# Pack_monitoring.net
KiCad netlist of a schematic drawn in Altium Designer
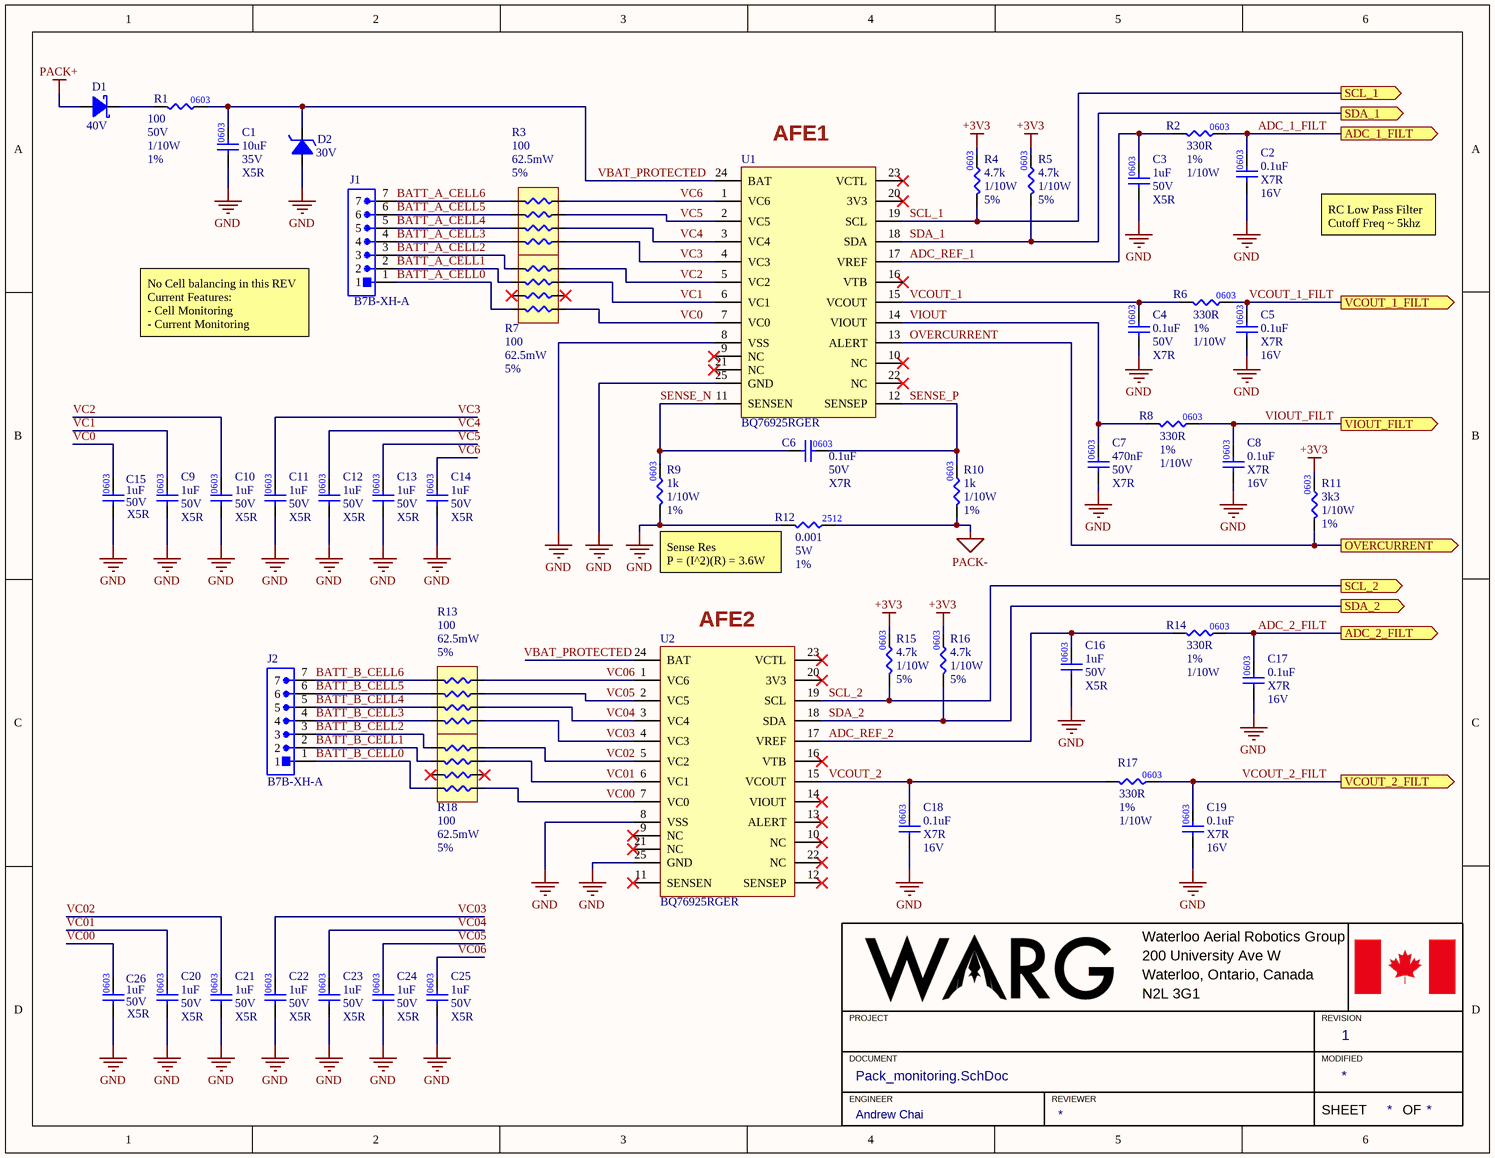
[diagram p0: Pack_monitoring.SchDoc]

(export (version "E")
  (design (tool "Eeschema 10.0.6"))
  (components
    (comp (ref "C1")
      (value "10uF")
      (footprint ".CAP_0603-Footprint-1")
      (fields
        (field (name "RATED DC VOLTAGE (URDC)") "35V")
        (field (name "TEMPERATURE CHARACTERISTICS CODE") "X5R")
        (field (name "Comment") "GRM188R6YA106MA73J")
      )
      (libsource (lib "WARG") (part ".CAP_0603-Symbol-1"))
    )
    (comp (ref "C2")
      (value "0.1uF")
      (footprint ".CAP_0603-Footprint-1")
      (description "CAP CER 0.1uF 16V X7R 0603")
      (fields
        (field (name "TEMPERATURE COEFFICIENT") "X7R")
        (field (name "VOLTAGE") "16V")
        (field (name "Comment") "GCM188R71C104KA37D")
      )
      (libsource (lib "WARG") (part ".CAP_0603-Symbol-1"))
    )
    (comp (ref "C3")
      (value "1uF")
      (footprint ".CAP_0603-Footprint-1")
      (description "CAP CER 1UF 50V X5R 0603")
      (fields
        (field (name "VOLTAGE RATING") "50V")
        (field (name "TEMPERATURE CHARACTERISTICS CODE") "X5R")
        (field (name "TOLERANCE") "10%")
        (field (name "Comment") "GRT188R61H105KE13D")
      )
      (libsource (lib "WARG") (part "CAP"))
    )
    (comp (ref "C4")
      (value "GCM188R71H104KA57D")
      (footprint "CAP0603")
      (description "CAP CER 0.1uF 50V X7R 0603")
      (fields
        (field (name "VOLTAGE") "50V")
        (field (name "DIELECTRIC") "X7R")
        (field (name "CAPACITANCE") "0.1uF")
        (field (name "TOLERANCE") "10%")
      )
      (libsource (lib "WARG") (part "CAP-NP-2"))
    )
    (comp (ref "C5")
      (value "0.1uF")
      (footprint ".CAP_0603-Footprint-1")
      (description "CAP CER 0.1uF 16V X7R 0603")
      (fields
        (field (name "TEMPERATURE COEFFICIENT") "X7R")
        (field (name "VOLTAGE") "16V")
        (field (name "Comment") "GCM188R71C104KA37D")
      )
      (libsource (lib "WARG") (part ".CAP_0603-Symbol-1"))
    )
    (comp (ref "C6")
      (value "GCM188R71H104KA57D")
      (footprint "CAP0603")
      (description "CAP CER 0.1uF 50V X7R 0603")
      (fields
        (field (name "VOLTAGE") "50V")
        (field (name "DIELECTRIC") "X7R")
        (field (name "CAPACITANCE") "0.1uF")
        (field (name "TOLERANCE") "10%")
      )
      (libsource (lib "WARG") (part "CAP-NP-2"))
    )
    (comp (ref "C7")
      (value "UMK107B7474KA-TR")
      (footprint "FP-0603-L_1_6_0_1-W_0_8_0-IPC_A")
      (description "0603 0.47 uF 50 V ±10% Tolerance X7R Multilayer Ceramic Capacitor")
      (fields
        (field (name "TOLERANCE") "10%")
        (field (name "DIELECTRIC") "X7R")
        (field (name "VOLTAGE") "50V")
        (field (name "CAPACITANCE") "470nF")
        (field (name "VOLTAGE RATING") "50V")
      )
      (libsource (lib "WARG") (part "02cd4be3c70576c341d710602a673aa"))
    )
    (comp (ref "C8")
      (value "0.1uF")
      (footprint ".CAP_0603-Footprint-1")
      (description "CAP CER 0.1uF 16V X7R 0603")
      (fields
        (field (name "TEMPERATURE COEFFICIENT") "X7R")
        (field (name "VOLTAGE") "16V")
        (field (name "Comment") "GCM188R71C104KA37D")
      )
      (libsource (lib "WARG") (part ".CAP_0603-Symbol-1"))
    )
    (comp (ref "C9")
      (value "1uF")
      (footprint ".CAP_0603-Footprint-1")
      (description "CAP CER 1UF 50V X5R 0603")
      (fields
        (field (name "VOLTAGE RATING") "50V")
        (field (name "TEMPERATURE CHARACTERISTICS CODE") "X5R")
        (field (name "TOLERANCE") "10%")
        (field (name "Comment") "GRT188R61H105KE13D")
      )
      (libsource (lib "WARG") (part "CAP"))
    )
    (comp (ref "C10")
      (value "1uF")
      (footprint ".CAP_0603-Footprint-1")
      (description "CAP CER 1UF 50V X5R 0603")
      (fields
        (field (name "VOLTAGE RATING") "50V")
        (field (name "TEMPERATURE CHARACTERISTICS CODE") "X5R")
        (field (name "TOLERANCE") "10%")
        (field (name "Comment") "GRT188R61H105KE13D")
      )
      (libsource (lib "WARG") (part "CAP"))
    )
    (comp (ref "C11")
      (value "1uF")
      (footprint ".CAP_0603-Footprint-1")
      (description "CAP CER 1UF 50V X5R 0603")
      (fields
        (field (name "VOLTAGE RATING") "50V")
        (field (name "TEMPERATURE CHARACTERISTICS CODE") "X5R")
        (field (name "TOLERANCE") "10%")
        (field (name "Comment") "GRT188R61H105KE13D")
      )
      (libsource (lib "WARG") (part "CAP"))
    )
    (comp (ref "C12")
      (value "1uF")
      (footprint ".CAP_0603-Footprint-1")
      (description "CAP CER 1UF 50V X5R 0603")
      (fields
        (field (name "VOLTAGE RATING") "50V")
        (field (name "TEMPERATURE CHARACTERISTICS CODE") "X5R")
        (field (name "TOLERANCE") "10%")
        (field (name "Comment") "GRT188R61H105KE13D")
      )
      (libsource (lib "WARG") (part "CAP"))
    )
    (comp (ref "C13")
      (value "1uF")
      (footprint ".CAP_0603-Footprint-1")
      (description "CAP CER 1UF 50V X5R 0603")
      (fields
        (field (name "VOLTAGE RATING") "50V")
        (field (name "TEMPERATURE CHARACTERISTICS CODE") "X5R")
        (field (name "TOLERANCE") "10%")
        (field (name "Comment") "GRT188R61H105KE13D")
      )
      (libsource (lib "WARG") (part "CAP"))
    )
    (comp (ref "C14")
      (value "1uF")
      (footprint ".CAP_0603-Footprint-1")
      (description "CAP CER 1UF 50V X5R 0603")
      (fields
        (field (name "VOLTAGE RATING") "50V")
        (field (name "TEMPERATURE CHARACTERISTICS CODE") "X5R")
        (field (name "TOLERANCE") "10%")
        (field (name "Comment") "GRT188R61H105KE13D")
      )
      (libsource (lib "WARG") (part "CAP"))
    )
    (comp (ref "C15")
      (value "1uF")
      (footprint ".CAP_0603-Footprint-1")
      (description "CAP CER 1UF 50V X5R 0603")
      (fields
        (field (name "VOLTAGE RATING") "50V")
        (field (name "TEMPERATURE CHARACTERISTICS CODE") "X5R")
        (field (name "TOLERANCE") "10%")
        (field (name "Comment") "GRT188R61H105KE13D")
      )
      (libsource (lib "WARG") (part "CAP"))
    )
    (comp (ref "C16")
      (value "1uF")
      (footprint ".CAP_0603-Footprint-1")
      (description "CAP CER 1UF 50V X5R 0603")
      (fields
        (field (name "VOLTAGE RATING") "50V")
        (field (name "TEMPERATURE CHARACTERISTICS CODE") "X5R")
        (field (name "TOLERANCE") "10%")
        (field (name "Comment") "GRT188R61H105KE13D")
      )
      (libsource (lib "WARG") (part "CAP"))
    )
    (comp (ref "C17")
      (value "0.1uF")
      (footprint ".CAP_0603-Footprint-1")
      (description "CAP CER 0.1uF 16V X7R 0603")
      (fields
        (field (name "TEMPERATURE COEFFICIENT") "X7R")
        (field (name "VOLTAGE") "16V")
        (field (name "Comment") "GCM188R71C104KA37D")
      )
      (libsource (lib "WARG") (part ".CAP_0603-Symbol-1"))
    )
    (comp (ref "C18")
      (value "0.1uF")
      (footprint ".CAP_0603-Footprint-1")
      (description "CAP CER 0.1uF 16V X7R 0603")
      (fields
        (field (name "TEMPERATURE COEFFICIENT") "X7R")
        (field (name "VOLTAGE") "16V")
        (field (name "Comment") "GCM188R71C104KA37D")
      )
      (libsource (lib "WARG") (part ".CAP_0603-Symbol-1"))
    )
    (comp (ref "C19")
      (value "0.1uF")
      (footprint ".CAP_0603-Footprint-1")
      (description "CAP CER 0.1uF 16V X7R 0603")
      (fields
        (field (name "TEMPERATURE COEFFICIENT") "X7R")
        (field (name "VOLTAGE") "16V")
        (field (name "Comment") "GCM188R71C104KA37D")
      )
      (libsource (lib "WARG") (part ".CAP_0603-Symbol-1"))
    )
    (comp (ref "C20")
      (value "1uF")
      (footprint ".CAP_0603-Footprint-1")
      (description "CAP CER 1UF 50V X5R 0603")
      (fields
        (field (name "VOLTAGE RATING") "50V")
        (field (name "TEMPERATURE CHARACTERISTICS CODE") "X5R")
        (field (name "TOLERANCE") "10%")
        (field (name "Comment") "GRT188R61H105KE13D")
      )
      (libsource (lib "WARG") (part "CAP"))
    )
    (comp (ref "C21")
      (value "1uF")
      (footprint ".CAP_0603-Footprint-1")
      (description "CAP CER 1UF 50V X5R 0603")
      (fields
        (field (name "VOLTAGE RATING") "50V")
        (field (name "TEMPERATURE CHARACTERISTICS CODE") "X5R")
        (field (name "TOLERANCE") "10%")
        (field (name "Comment") "GRT188R61H105KE13D")
      )
      (libsource (lib "WARG") (part "CAP"))
    )
    (comp (ref "C22")
      (value "1uF")
      (footprint ".CAP_0603-Footprint-1")
      (description "CAP CER 1UF 50V X5R 0603")
      (fields
        (field (name "VOLTAGE RATING") "50V")
        (field (name "TEMPERATURE CHARACTERISTICS CODE") "X5R")
        (field (name "TOLERANCE") "10%")
        (field (name "Comment") "GRT188R61H105KE13D")
      )
      (libsource (lib "WARG") (part "CAP"))
    )
    (comp (ref "C23")
      (value "1uF")
      (footprint ".CAP_0603-Footprint-1")
      (description "CAP CER 1UF 50V X5R 0603")
      (fields
        (field (name "VOLTAGE RATING") "50V")
        (field (name "TEMPERATURE CHARACTERISTICS CODE") "X5R")
        (field (name "TOLERANCE") "10%")
        (field (name "Comment") "GRT188R61H105KE13D")
      )
      (libsource (lib "WARG") (part "CAP"))
    )
    (comp (ref "C24")
      (value "1uF")
      (footprint ".CAP_0603-Footprint-1")
      (description "CAP CER 1UF 50V X5R 0603")
      (fields
        (field (name "VOLTAGE RATING") "50V")
        (field (name "TEMPERATURE CHARACTERISTICS CODE") "X5R")
        (field (name "TOLERANCE") "10%")
        (field (name "Comment") "GRT188R61H105KE13D")
      )
      (libsource (lib "WARG") (part "CAP"))
    )
    (comp (ref "C25")
      (value "1uF")
      (footprint ".CAP_0603-Footprint-1")
      (description "CAP CER 1UF 50V X5R 0603")
      (fields
        (field (name "VOLTAGE RATING") "50V")
        (field (name "TEMPERATURE CHARACTERISTICS CODE") "X5R")
        (field (name "TOLERANCE") "10%")
        (field (name "Comment") "GRT188R61H105KE13D")
      )
      (libsource (lib "WARG") (part "CAP"))
    )
    (comp (ref "C26")
      (value "1uF")
      (footprint ".CAP_0603-Footprint-1")
      (description "CAP CER 1UF 50V X5R 0603")
      (fields
        (field (name "VOLTAGE RATING") "50V")
        (field (name "TEMPERATURE CHARACTERISTICS CODE") "X5R")
        (field (name "TOLERANCE") "10%")
        (field (name "Comment") "GRT188R61H105KE13D")
      )
      (libsource (lib "WARG") (part "CAP"))
    )
    (comp (ref "D1")
      (value "MBR0540T1G")
      (footprint "Copy of .SCHOTTKY-Footprint-1")
      (description "DIODE SCHOTTKY 40V 500MA SOD123")
      (fields (field (name "REP PK REVERSE VOLTAGE-MAX") "40V"))
      (libsource (lib "WARG") (part ".SCHOTTKY-Symbol-1"))
    )
    (comp (ref "D2")
      (value "BZT52C30-13")
      (footprint "BZT52C30-13-Footprint-1")
      (description "Zener Diode, 30V V(Z), 6.67%, 0.5W, Silicon, Unidirectional")
      (fields (field (name "REFERENCE VOLTAGE-NOM") "30V"))
      (libsource (lib "WARG") (part ".ZENER-Symbol-1"))
    )
    (comp (ref "J1")
      (value "B7B-XH-A")
      (footprint "B7B-XH-A")
      (description "Header B7B-XH-A, 2.50mm, 7-contacts, top entry, THT /500/box")
      (fields (field (name "MF") "JST Sales"))
      (libsource (lib "WARG") (part "B7B-XH-A"))
    )
    (comp (ref "J2")
      (value "B7B-XH-A")
      (footprint "B7B-XH-A")
      (description "Header B7B-XH-A, 2.50mm, 7-contacts, top entry, THT /500/box")
      (fields (field (name "MF") "JST Sales"))
      (libsource (lib "WARG") (part "B7B-XH-A"))
    )
    (comp (ref "R1")
      (value "RC0603FR-07100RL")
      (footprint ".RES_0603-Footprint-1")
      (description "RES 100 OHM 1% 1/10W 0603")
      (fields
        (field (name "RESISTANCE") "100")
        (field (name "VOLTAGE RATING (DC)") "50V")
        (field (name "POWER RATING") "1/10W")
        (field (name "TOLERANCE") "1%")
      )
      (libsource (lib "") (part ".RES_0603-Symbol-1_1"))
    )
    (comp (ref "R2")
      (value "330R")
      (footprint ".RES_0603-Footprint-1")
      (fields
        (field (name "POWER") "1/10W")
        (field (name "TOLERANCE") "1%")
        (field (name "Comment") "AF0603FR-07330RL")
      )
      (libsource (lib "") (part ".RES_0603-Symbol-1_1"))
    )
    (comp (ref "R3")
      (value "100")
      (footprint ".RES_0603-Footprint-1")
      (description "YC124 Series 4 Elements 100 Ohms 5 % Case 4 x 0402 SMD Chip Resistor Network")
      (fields
        (field (name "POWER") "62.5mW")
        (field (name "TOLERANCE") "5%")
        (field (name "Comment") "YC124JR-07100RL")
      )
      (libsource (lib "WARG") (part "YC124-JR-07100RL"))
    )
    (comp (ref "R4")
      (value "4.7k")
      (footprint ".RES_0603-Footprint-1")
      (description "RES 4.7K OHM 5% 1/10W 0603")
      (fields
        (field (name "RESISTANCE TOLERANCE") "5%")
        (field (name "POWER RATING") "1/10W")
        (field (name "Comment") "RC0603JR-074K7L")
      )
      (libsource (lib "") (part ".RES_0603-Symbol-1_1"))
    )
    (comp (ref "R5")
      (value "4.7k")
      (footprint ".RES_0603-Footprint-1")
      (description "RES 4.7K OHM 5% 1/10W 0603")
      (fields
        (field (name "RESISTANCE TOLERANCE") "5%")
        (field (name "POWER RATING") "1/10W")
        (field (name "Comment") "RC0603JR-074K7L")
      )
      (libsource (lib "") (part ".RES_0603-Symbol-1_1"))
    )
    (comp (ref "R6")
      (value "330R")
      (footprint ".RES_0603-Footprint-1")
      (fields
        (field (name "POWER") "1/10W")
        (field (name "TOLERANCE") "1%")
        (field (name "Comment") "AF0603FR-07330RL")
      )
      (libsource (lib "") (part ".RES_0603-Symbol-1_1"))
    )
    (comp (ref "R7")
      (value "100")
      (footprint ".RES_0603-Footprint-1")
      (description "YC124 Series 4 Elements 100 Ohms 5 % Case 4 x 0402 SMD Chip Resistor Network")
      (fields
        (field (name "POWER") "62.5mW")
        (field (name "TOLERANCE") "5%")
        (field (name "Comment") "YC124JR-07100RL")
      )
      (libsource (lib "WARG") (part "YC124-JR-07100RL"))
    )
    (comp (ref "R8")
      (value "330R")
      (footprint ".RES_0603-Footprint-1")
      (fields
        (field (name "POWER") "1/10W")
        (field (name "TOLERANCE") "1%")
        (field (name "Comment") "AF0603FR-07330RL")
      )
      (libsource (lib "") (part ".RES_0603-Symbol-1_1"))
    )
    (comp (ref "R9")
      (value "1k")
      (footprint ".RES_0603-Footprint-1")
      (description "RES 1k OHM 1% 1/10W 0603")
      (fields
        (field (name "POWER") "1/10W")
        (field (name "TOLERANCE") "1%")
        (field (name "Comment") "RC0603FR-071KL")
      )
      (libsource (lib "") (part ".RES_0603-Symbol-1_1"))
    )
    (comp (ref "R10")
      (value "1k")
      (footprint ".RES_0603-Footprint-1")
      (description "RES 1k OHM 1% 1/10W 0603")
      (fields
        (field (name "POWER") "1/10W")
        (field (name "TOLERANCE") "1%")
        (field (name "Comment") "RC0603FR-071KL")
      )
      (libsource (lib "") (part ".RES_0603-Symbol-1_1"))
    )
    (comp (ref "R11")
      (value "3k3")
      (footprint ".RES_0603-Footprint-1")
      (description "RES 3.3K OHM 1% 1/10W 0603")
      (fields
        (field (name "POWER") "1/10W")
        (field (name "TOLERANCE") "1%")
        (field (name "Comment") "RC0603FR-103K3L")
      )
      (libsource (lib "") (part ".RES_0603-Symbol-1_1"))
    )
    (comp (ref "R12")
      (value "0.001")
      (footprint ".RES_0603-Footprint-1")
      (description "Fixed Resistor, Metal Strip, 5W, 0.001ohm, 1% +/-Tol, 50ppm/Cel, Surface Mount, 2512")
      (fields
        (field (name "TOLERANCE") "1%")
        (field (name "POWER") "5W")
        (field (name "Comment") "CSS2H-2512R-1L00F")
      )
      (libsource (lib "WARG") (part ".RES_0603-Symbol-1"))
    )
    (comp (ref "R13")
      (value "100")
      (footprint ".RES_0603-Footprint-1")
      (description "YC124 Series 4 Elements 100 Ohms 5 % Case 4 x 0402 SMD Chip Resistor Network")
      (fields
        (field (name "POWER") "62.5mW")
        (field (name "TOLERANCE") "5%")
        (field (name "Comment") "YC124JR-07100RL")
      )
      (libsource (lib "WARG") (part "YC124-JR-07100RL"))
    )
    (comp (ref "R14")
      (value "330R")
      (footprint ".RES_0603-Footprint-1")
      (fields
        (field (name "POWER") "1/10W")
        (field (name "TOLERANCE") "1%")
        (field (name "Comment") "AF0603FR-07330RL")
      )
      (libsource (lib "") (part ".RES_0603-Symbol-1_1"))
    )
    (comp (ref "R15")
      (value "4.7k")
      (footprint ".RES_0603-Footprint-1")
      (description "RES 4.7K OHM 5% 1/10W 0603")
      (fields
        (field (name "RESISTANCE TOLERANCE") "5%")
        (field (name "POWER RATING") "1/10W")
        (field (name "Comment") "RC0603JR-074K7L")
      )
      (libsource (lib "") (part ".RES_0603-Symbol-1_1"))
    )
    (comp (ref "R16")
      (value "4.7k")
      (footprint ".RES_0603-Footprint-1")
      (description "RES 4.7K OHM 5% 1/10W 0603")
      (fields
        (field (name "RESISTANCE TOLERANCE") "5%")
        (field (name "POWER RATING") "1/10W")
        (field (name "Comment") "RC0603JR-074K7L")
      )
      (libsource (lib "") (part ".RES_0603-Symbol-1_1"))
    )
    (comp (ref "R17")
      (value "330R")
      (footprint ".RES_0603-Footprint-1")
      (fields
        (field (name "POWER") "1/10W")
        (field (name "TOLERANCE") "1%")
        (field (name "Comment") "AF0603FR-07330RL")
      )
      (libsource (lib "") (part ".RES_0603-Symbol-1_1"))
    )
    (comp (ref "R18")
      (value "100")
      (footprint ".RES_0603-Footprint-1")
      (description "YC124 Series 4 Elements 100 Ohms 5 % Case 4 x 0402 SMD Chip Resistor Network")
      (fields
        (field (name "POWER") "62.5mW")
        (field (name "TOLERANCE") "5%")
        (field (name "Comment") "YC124JR-07100RL")
      )
      (libsource (lib "WARG") (part "YC124-JR-07100RL"))
    )
    (comp (ref "U1")
      (value "BQ76925RGER")
      (footprint "QFN50P400X400X100_HS-25N")
      (description "Power Supply Support Circuit, Adjustable, 1 Channel, PQCC24")
      (libsource (lib "WARG") (part "BQ76925PWR"))
    )
    (comp (ref "U2")
      (value "BQ76925RGER")
      (footprint "QFN50P400X400X100_HS-25N")
      (description "Power Supply Support Circuit, Adjustable, 1 Channel, PQCC24")
      (libsource (lib "WARG") (part "BQ76925PWR"))
    )
  )
  (nets
    (net (code "1") (name "+3V3") (class "Default")
      (node (ref "R11") (pin "2") (pinfunction "2_2") (pintype "passive"))
      (node (ref "R15") (pin "2") (pinfunction "2_2") (pintype "passive"))
      (node (ref "R16") (pin "2") (pinfunction "2_2") (pintype "passive"))
      (node (ref "R4") (pin "2") (pinfunction "2_2") (pintype "passive"))
      (node (ref "R5") (pin "2") (pinfunction "2_2") (pintype "passive"))
    )
    (net (code "2") (name "/ADC_1_FILT") (class "Default")
      (node (ref "C2") (pin "2") (pinfunction "2_2") (pintype "passive"))
      (node (ref "R2") (pin "2") (pinfunction "2_2") (pintype "passive"))
    )
    (net (code "3") (name "/ADC_2_FILT") (class "Default")
      (node (ref "C17") (pin "2") (pinfunction "2_2") (pintype "passive"))
      (node (ref "R14") (pin "2") (pinfunction "2_2") (pintype "passive"))
    )
    (net (code "4") (name "/ADC_REF_1") (class "Default")
      (node (ref "C3") (pin "2") (pinfunction "2_2") (pintype "passive"))
      (node (ref "R2") (pin "1") (pinfunction "1_1") (pintype "passive"))
      (node (ref "U1") (pin "17") (pinfunction "VREF_17") (pintype "passive"))
    )
    (net (code "5") (name "/ADC_REF_2") (class "Default")
      (node (ref "C16") (pin "2") (pinfunction "2_2") (pintype "passive"))
      (node (ref "R14") (pin "1") (pinfunction "1_1") (pintype "passive"))
      (node (ref "U2") (pin "17") (pinfunction "VREF_17") (pintype "passive"))
    )
    (net (code "6") (name "/BATT_A_CELL0") (class "Default")
      (node (ref "J1") (pin "1") (pinfunction "1_1") (pintype "passive"))
      (node (ref "R7") (pin "7") (pinfunction "7_7") (pintype "passive"))
    )
    (net (code "7") (name "/BATT_A_CELL1") (class "Default")
      (node (ref "J1") (pin "2") (pinfunction "2_2") (pintype "passive"))
      (node (ref "R7") (pin "3") (pinfunction "3_3") (pintype "passive"))
    )
    (net (code "8") (name "/BATT_A_CELL2") (class "Default")
      (node (ref "J1") (pin "3") (pinfunction "3_3") (pintype "passive"))
      (node (ref "R7") (pin "1") (pinfunction "1_1") (pintype "passive"))
    )
    (net (code "9") (name "/BATT_A_CELL3") (class "Default")
      (node (ref "J1") (pin "4") (pinfunction "4_4") (pintype "passive"))
      (node (ref "R3") (pin "7") (pinfunction "7_7") (pintype "passive"))
    )
    (net (code "10") (name "/BATT_A_CELL4") (class "Default")
      (node (ref "J1") (pin "5") (pinfunction "5_5") (pintype "passive"))
      (node (ref "R3") (pin "5") (pinfunction "5_5") (pintype "passive"))
    )
    (net (code "11") (name "/BATT_A_CELL5") (class "Default")
      (node (ref "J1") (pin "6") (pinfunction "6_6") (pintype "passive"))
      (node (ref "R3") (pin "3") (pinfunction "3_3") (pintype "passive"))
    )
    (net (code "12") (name "/BATT_A_CELL6") (class "Default")
      (node (ref "J1") (pin "7") (pinfunction "7_7") (pintype "passive"))
      (node (ref "R3") (pin "1") (pinfunction "1_1") (pintype "passive"))
    )
    (net (code "13") (name "/BATT_B_CELL0") (class "Default")
      (node (ref "J2") (pin "1") (pinfunction "1_1") (pintype "passive"))
      (node (ref "R18") (pin "7") (pinfunction "7_7") (pintype "passive"))
    )
    (net (code "14") (name "/BATT_B_CELL1") (class "Default")
      (node (ref "J2") (pin "2") (pinfunction "2_2") (pintype "passive"))
      (node (ref "R18") (pin "3") (pinfunction "3_3") (pintype "passive"))
    )
    (net (code "15") (name "/BATT_B_CELL2") (class "Default")
      (node (ref "J2") (pin "3") (pinfunction "3_3") (pintype "passive"))
      (node (ref "R18") (pin "1") (pinfunction "1_1") (pintype "passive"))
    )
    (net (code "16") (name "/BATT_B_CELL3") (class "Default")
      (node (ref "J2") (pin "4") (pinfunction "4_4") (pintype "passive"))
      (node (ref "R13") (pin "7") (pinfunction "7_7") (pintype "passive"))
    )
    (net (code "17") (name "/BATT_B_CELL4") (class "Default")
      (node (ref "J2") (pin "5") (pinfunction "5_5") (pintype "passive"))
      (node (ref "R13") (pin "5") (pinfunction "5_5") (pintype "passive"))
    )
    (net (code "18") (name "/BATT_B_CELL5") (class "Default")
      (node (ref "J2") (pin "6") (pinfunction "6_6") (pintype "passive"))
      (node (ref "R13") (pin "3") (pinfunction "3_3") (pintype "passive"))
    )
    (net (code "19") (name "/BATT_B_CELL6") (class "Default")
      (node (ref "J2") (pin "7") (pinfunction "7_7") (pintype "passive"))
      (node (ref "R13") (pin "1") (pinfunction "1_1") (pintype "passive"))
    )
    (net (code "20") (name "/OVERCURRENT") (class "Default")
      (node (ref "R11") (pin "1") (pinfunction "1_1") (pintype "passive"))
      (node (ref "U1") (pin "13") (pinfunction "ALERT_13") (pintype "passive"))
    )
    (net (code "21") (name "/SCL_1") (class "Default")
      (node (ref "R4") (pin "1") (pinfunction "1_1") (pintype "passive"))
      (node (ref "U1") (pin "19") (pinfunction "SCL_19") (pintype "passive"))
    )
    (net (code "22") (name "/SCL_2") (class "Default")
      (node (ref "R15") (pin "1") (pinfunction "1_1") (pintype "passive"))
      (node (ref "U2") (pin "19") (pinfunction "SCL_19") (pintype "passive"))
    )
    (net (code "23") (name "/SDA_1") (class "Default")
      (node (ref "R5") (pin "1") (pinfunction "1_1") (pintype "passive"))
      (node (ref "U1") (pin "18") (pinfunction "SDA_18") (pintype "passive"))
    )
    (net (code "24") (name "/SDA_2") (class "Default")
      (node (ref "R16") (pin "1") (pinfunction "1_1") (pintype "passive"))
      (node (ref "U2") (pin "18") (pinfunction "SDA_18") (pintype "passive"))
    )
    (net (code "25") (name "/SENSE_N") (class "Default")
      (node (ref "C6") (pin "1") (pinfunction "1_1") (pintype "passive"))
      (node (ref "R9") (pin "2") (pinfunction "2_2") (pintype "passive"))
      (node (ref "U1") (pin "11") (pinfunction "SENSEN_11") (pintype "passive"))
    )
    (net (code "26") (name "/SENSE_P") (class "Default")
      (node (ref "C6") (pin "2") (pinfunction "2_2") (pintype "passive"))
      (node (ref "R10") (pin "2") (pinfunction "2_2") (pintype "passive"))
      (node (ref "U1") (pin "12") (pinfunction "SENSEP_12") (pintype "passive"))
    )
    (net (code "27") (name "/VBAT_PROTECTED") (class "Default")
      (node (ref "C1") (pin "2") (pinfunction "2_2") (pintype "passive"))
      (node (ref "D2") (pin "2") (pinfunction "Cathode_2") (pintype "passive"))
      (node (ref "R1") (pin "2") (pinfunction "2_2") (pintype "passive"))
      (node (ref "U1") (pin "24") (pinfunction "BAT_24") (pintype "passive"))
      (node (ref "U2") (pin "24") (pinfunction "BAT_24") (pintype "passive"))
    )
    (net (code "28") (name "/VC0") (class "Default")
      (node (ref "C15") (pin "2") (pinfunction "2_2") (pintype "passive"))
      (node (ref "R7") (pin "8") (pinfunction "8_8") (pintype "passive"))
      (node (ref "U1") (pin "7") (pinfunction "VC0_7") (pintype "passive"))
    )
    (net (code "29") (name "/VC00") (class "Default")
      (node (ref "C26") (pin "2") (pinfunction "2_2") (pintype "passive"))
      (node (ref "R18") (pin "8") (pinfunction "8_8") (pintype "passive"))
      (node (ref "U2") (pin "7") (pinfunction "VC0_7") (pintype "passive"))
    )
    (net (code "30") (name "/VC1") (class "Default")
      (node (ref "C9") (pin "2") (pinfunction "2_2") (pintype "passive"))
      (node (ref "R7") (pin "4") (pinfunction "4_4") (pintype "passive"))
      (node (ref "U1") (pin "6") (pinfunction "VC1_6") (pintype "passive"))
    )
    (net (code "31") (name "/VC01") (class "Default")
      (node (ref "C20") (pin "2") (pinfunction "2_2") (pintype "passive"))
      (node (ref "R18") (pin "4") (pinfunction "4_4") (pintype "passive"))
      (node (ref "U2") (pin "6") (pinfunction "VC1_6") (pintype "passive"))
    )
    (net (code "32") (name "/VC2") (class "Default")
      (node (ref "C10") (pin "2") (pinfunction "2_2") (pintype "passive"))
      (node (ref "R7") (pin "2") (pinfunction "2_2") (pintype "passive"))
      (node (ref "U1") (pin "5") (pinfunction "VC2_5") (pintype "passive"))
    )
    (net (code "33") (name "/VC02") (class "Default")
      (node (ref "C21") (pin "2") (pinfunction "2_2") (pintype "passive"))
      (node (ref "R18") (pin "2") (pinfunction "2_2") (pintype "passive"))
      (node (ref "U2") (pin "5") (pinfunction "VC2_5") (pintype "passive"))
    )
    (net (code "34") (name "/VC03") (class "Default")
      (node (ref "C22") (pin "2") (pinfunction "2_2") (pintype "passive"))
      (node (ref "R13") (pin "8") (pinfunction "8_8") (pintype "passive"))
      (node (ref "U2") (pin "4") (pinfunction "VC3_4") (pintype "passive"))
    )
    (net (code "35") (name "/VC3") (class "Default")
      (node (ref "C11") (pin "2") (pinfunction "2_2") (pintype "passive"))
      (node (ref "R3") (pin "8") (pinfunction "8_8") (pintype "passive"))
      (node (ref "U1") (pin "4") (pinfunction "VC3_4") (pintype "passive"))
    )
    (net (code "36") (name "/VC4") (class "Default")
      (node (ref "C12") (pin "2") (pinfunction "2_2") (pintype "passive"))
      (node (ref "R3") (pin "6") (pinfunction "6_6") (pintype "passive"))
      (node (ref "U1") (pin "3") (pinfunction "VC4_3") (pintype "passive"))
    )
    (net (code "37") (name "/VC04") (class "Default")
      (node (ref "C23") (pin "2") (pinfunction "2_2") (pintype "passive"))
      (node (ref "R13") (pin "6") (pinfunction "6_6") (pintype "passive"))
      (node (ref "U2") (pin "3") (pinfunction "VC4_3") (pintype "passive"))
    )
    (net (code "38") (name "/VC5") (class "Default")
      (node (ref "C13") (pin "2") (pinfunction "2_2") (pintype "passive"))
      (node (ref "R3") (pin "4") (pinfunction "4_4") (pintype "passive"))
      (node (ref "U1") (pin "2") (pinfunction "VC5_2") (pintype "passive"))
    )
    (net (code "39") (name "/VC05") (class "Default")
      (node (ref "C24") (pin "2") (pinfunction "2_2") (pintype "passive"))
      (node (ref "R13") (pin "4") (pinfunction "4_4") (pintype "passive"))
      (node (ref "U2") (pin "2") (pinfunction "VC5_2") (pintype "passive"))
    )
    (net (code "40") (name "/VC6") (class "Default")
      (node (ref "C14") (pin "2") (pinfunction "2_2") (pintype "passive"))
      (node (ref "R3") (pin "2") (pinfunction "2_2") (pintype "passive"))
      (node (ref "U1") (pin "1") (pinfunction "VC6_1") (pintype "passive"))
    )
    (net (code "41") (name "/VC06") (class "Default")
      (node (ref "C25") (pin "2") (pinfunction "2_2") (pintype "passive"))
      (node (ref "R13") (pin "2") (pinfunction "2_2") (pintype "passive"))
      (node (ref "U2") (pin "1") (pinfunction "VC6_1") (pintype "passive"))
    )
    (net (code "42") (name "/VCOUT_1") (class "Default")
      (node (ref "C4") (pin "2") (pinfunction "2_2") (pintype "passive"))
      (node (ref "R6") (pin "1") (pinfunction "1_1") (pintype "passive"))
      (node (ref "U1") (pin "15") (pinfunction "VCOUT_15") (pintype "passive"))
    )
    (net (code "43") (name "/VCOUT_1_FILT") (class "Default")
      (node (ref "C5") (pin "2") (pinfunction "2_2") (pintype "passive"))
      (node (ref "R6") (pin "2") (pinfunction "2_2") (pintype "passive"))
    )
    (net (code "44") (name "/VCOUT_2") (class "Default")
      (node (ref "C18") (pin "2") (pinfunction "2_2") (pintype "passive"))
      (node (ref "R17") (pin "1") (pinfunction "1_1") (pintype "passive"))
      (node (ref "U2") (pin "15") (pinfunction "VCOUT_15") (pintype "passive"))
    )
    (net (code "45") (name "/VCOUT_2_FILT") (class "Default")
      (node (ref "C19") (pin "2") (pinfunction "2_2") (pintype "passive"))
      (node (ref "R17") (pin "2") (pinfunction "2_2") (pintype "passive"))
    )
    (net (code "46") (name "/VIOUT") (class "Default")
      (node (ref "C7") (pin "2") (pinfunction "2_2") (pintype "passive"))
      (node (ref "R8") (pin "1") (pinfunction "1_1") (pintype "passive"))
      (node (ref "U1") (pin "14") (pinfunction "VIOUT_14") (pintype "passive"))
    )
    (net (code "47") (name "/VIOUT_FILT") (class "Default")
      (node (ref "C8") (pin "2") (pinfunction "2_2") (pintype "passive"))
      (node (ref "R8") (pin "2") (pinfunction "2_2") (pintype "passive"))
    )
    (net (code "48") (name "GND") (class "Default")
      (node (ref "C1") (pin "1") (pinfunction "1_1") (pintype "passive"))
      (node (ref "C10") (pin "1") (pinfunction "1_1") (pintype "passive"))
      (node (ref "C11") (pin "1") (pinfunction "1_1") (pintype "passive"))
      (node (ref "C12") (pin "1") (pinfunction "1_1") (pintype "passive"))
      (node (ref "C13") (pin "1") (pinfunction "1_1") (pintype "passive"))
      (node (ref "C14") (pin "1") (pinfunction "1_1") (pintype "passive"))
      (node (ref "C15") (pin "1") (pinfunction "1_1") (pintype "passive"))
      (node (ref "C16") (pin "1") (pinfunction "1_1") (pintype "passive"))
      (node (ref "C17") (pin "1") (pinfunction "1_1") (pintype "passive"))
      (node (ref "C18") (pin "1") (pinfunction "1_1") (pintype "passive"))
      (node (ref "C19") (pin "1") (pinfunction "1_1") (pintype "passive"))
      (node (ref "C2") (pin "1") (pinfunction "1_1") (pintype "passive"))
      (node (ref "C20") (pin "1") (pinfunction "1_1") (pintype "passive"))
      (node (ref "C21") (pin "1") (pinfunction "1_1") (pintype "passive"))
      (node (ref "C22") (pin "1") (pinfunction "1_1") (pintype "passive"))
      (node (ref "C23") (pin "1") (pinfunction "1_1") (pintype "passive"))
      (node (ref "C24") (pin "1") (pinfunction "1_1") (pintype "passive"))
      (node (ref "C25") (pin "1") (pinfunction "1_1") (pintype "passive"))
      (node (ref "C26") (pin "1") (pinfunction "1_1") (pintype "passive"))
      (node (ref "C3") (pin "1") (pinfunction "1_1") (pintype "passive"))
      (node (ref "C4") (pin "1") (pinfunction "1_1") (pintype "passive"))
      (node (ref "C5") (pin "1") (pinfunction "1_1") (pintype "passive"))
      (node (ref "C7") (pin "1") (pinfunction "1_1") (pintype "passive"))
      (node (ref "C8") (pin "1") (pinfunction "1_1") (pintype "passive"))
      (node (ref "C9") (pin "1") (pinfunction "1_1") (pintype "passive"))
      (node (ref "D2") (pin "1") (pinfunction "Anode_1") (pintype "passive"))
      (node (ref "R12") (pin "1") (pinfunction "1_1") (pintype "passive"))
      (node (ref "R9") (pin "1") (pinfunction "1_1") (pintype "passive"))
      (node (ref "U1") (pin "25") (pinfunction "GND_25") (pintype "passive"))
      (node (ref "U1") (pin "8") (pinfunction "VSS_8") (pintype "passive"))
      (node (ref "U2") (pin "25") (pinfunction "GND_25") (pintype "passive"))
      (node (ref "U2") (pin "8") (pinfunction "VSS_8") (pintype "passive"))
    )
    (net (code "49") (name "Net-(D1-Cathode)") (class "Default")
      (node (ref "D1") (pin "2") (pinfunction "Cathode_2") (pintype "passive"))
      (node (ref "R1") (pin "1") (pinfunction "1_1") (pintype "passive"))
    )
    (net (code "50") (name "PACK+") (class "Default")
      (node (ref "D1") (pin "1") (pinfunction "Anode_1") (pintype "passive"))
    )
    (net (code "51") (name "PACK-") (class "Default")
      (node (ref "R10") (pin "1") (pinfunction "1_1") (pintype "passive"))
      (node (ref "R12") (pin "2") (pinfunction "2_2") (pintype "passive"))
    )
    (net (code "52") (name "unconnected-(R7-Pad5)") (class "Default")
      (node (ref "R7") (pin "5") (pinfunction "5_5") (pintype "passive+no_connect"))
    )
    (net (code "53") (name "unconnected-(R7-Pad6)") (class "Default")
      (node (ref "R7") (pin "6") (pinfunction "6_6") (pintype "passive+no_connect"))
    )
    (net (code "54") (name "unconnected-(R18-Pad5)") (class "Default")
      (node (ref "R18") (pin "5") (pinfunction "5_5") (pintype "passive+no_connect"))
    )
    (net (code "55") (name "unconnected-(R18-Pad6)") (class "Default")
      (node (ref "R18") (pin "6") (pinfunction "6_6") (pintype "passive+no_connect"))
    )
    (net (code "56") (name "unconnected-(U1-3V3-Pad20)") (class "Default")
      (node (ref "U1") (pin "20") (pinfunction "3V3_20") (pintype "passive+no_connect"))
    )
    (net (code "57") (name "unconnected-(U1-NC-Pad9)") (class "Default")
      (node (ref "U1") (pin "9") (pinfunction "NC_9") (pintype "passive+no_connect"))
    )
    (net (code "58") (name "unconnected-(U1-NC-Pad10)") (class "Default")
      (node (ref "U1") (pin "10") (pinfunction "NC_10") (pintype "passive+no_connect"))
    )
    (net (code "59") (name "unconnected-(U1-NC-Pad21)") (class "Default")
      (node (ref "U1") (pin "21") (pinfunction "NC_21") (pintype "passive+no_connect"))
    )
    (net (code "60") (name "unconnected-(U1-NC-Pad22)") (class "Default")
      (node (ref "U1") (pin "22") (pinfunction "NC_22") (pintype "passive+no_connect"))
    )
    (net (code "61") (name "unconnected-(U1-VCTL-Pad23)") (class "Default")
      (node (ref "U1") (pin "23") (pinfunction "VCTL_23") (pintype "passive+no_connect"))
    )
    (net (code "62") (name "unconnected-(U1-VTB-Pad16)") (class "Default")
      (node (ref "U1") (pin "16") (pinfunction "VTB_16") (pintype "passive+no_connect"))
    )
    (net (code "63") (name "unconnected-(U2-3V3-Pad20)") (class "Default")
      (node (ref "U2") (pin "20") (pinfunction "3V3_20") (pintype "passive+no_connect"))
    )
    (net (code "64") (name "unconnected-(U2-ALERT-Pad13)") (class "Default")
      (node (ref "U2") (pin "13") (pinfunction "ALERT_13") (pintype "passive+no_connect"))
    )
    (net (code "65") (name "unconnected-(U2-NC-Pad9)") (class "Default")
      (node (ref "U2") (pin "9") (pinfunction "NC_9") (pintype "passive+no_connect"))
    )
    (net (code "66") (name "unconnected-(U2-NC-Pad10)") (class "Default")
      (node (ref "U2") (pin "10") (pinfunction "NC_10") (pintype "passive+no_connect"))
    )
    (net (code "67") (name "unconnected-(U2-NC-Pad21)") (class "Default")
      (node (ref "U2") (pin "21") (pinfunction "NC_21") (pintype "passive+no_connect"))
    )
    (net (code "68") (name "unconnected-(U2-NC-Pad22)") (class "Default")
      (node (ref "U2") (pin "22") (pinfunction "NC_22") (pintype "passive+no_connect"))
    )
    (net (code "69") (name "unconnected-(U2-SENSEN-Pad11)") (class "Default")
      (node (ref "U2") (pin "11") (pinfunction "SENSEN_11") (pintype "passive+no_connect"))
    )
    (net (code "70") (name "unconnected-(U2-SENSEP-Pad12)") (class "Default")
      (node (ref "U2") (pin "12") (pinfunction "SENSEP_12") (pintype "passive+no_connect"))
    )
    (net (code "71") (name "unconnected-(U2-VCTL-Pad23)") (class "Default")
      (node (ref "U2") (pin "23") (pinfunction "VCTL_23") (pintype "passive+no_connect"))
    )
    (net (code "72") (name "unconnected-(U2-VIOUT-Pad14)") (class "Default")
      (node (ref "U2") (pin "14") (pinfunction "VIOUT_14") (pintype "passive+no_connect"))
    )
    (net (code "73") (name "unconnected-(U2-VTB-Pad16)") (class "Default")
      (node (ref "U2") (pin "16") (pinfunction "VTB_16") (pintype "passive+no_connect"))
    )
  )
)
